# WATER_LEVEL_INDICATOR.net
KiCad netlist of a schematic drawn in EAGLE
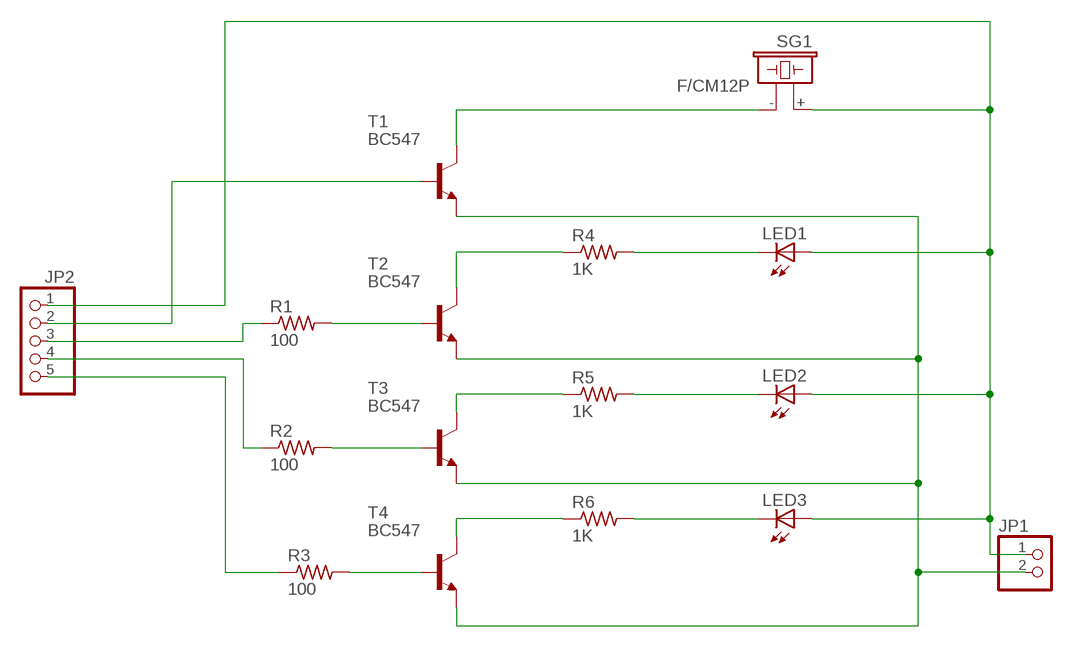
[diagram p0: schematic, sheet 1]

(export (version "E")
  (design (tool "Eeschema 10.0.6"))
  (components
    (comp (ref "JP1")
      (value "PINHD-1X2")
      (footprint "eagle-import:1X02")
      (libsource (lib "eagle-import") (part "PINHD-1X2"))
    )
    (comp (ref "JP2")
      (value "PINHD-1X5")
      (footprint "eagle-import:1X05")
      (libsource (lib "eagle-import") (part "PINHD-1X5"))
    )
    (comp (ref "LED1")
      (value "LED5MM")
      (footprint "eagle-import:LED5MM")
      (libsource (lib "eagle-import") (part "LED5MM"))
    )
    (comp (ref "LED2")
      (value "LED5MM")
      (footprint "eagle-import:LED5MM")
      (libsource (lib "eagle-import") (part "LED5MM"))
    )
    (comp (ref "LED3")
      (value "LED5MM")
      (footprint "eagle-import:LED5MM")
      (libsource (lib "eagle-import") (part "LED5MM"))
    )
    (comp (ref "R1")
      (value "100")
      (footprint "eagle-import:0207_10")
      (libsource (lib "eagle-import") (part "R-US_0207/10"))
    )
    (comp (ref "R2")
      (value "100")
      (footprint "eagle-import:0207_10")
      (libsource (lib "eagle-import") (part "R-US_0207/10"))
    )
    (comp (ref "R3")
      (value "100")
      (footprint "eagle-import:0207_10")
      (libsource (lib "eagle-import") (part "R-US_0207/10"))
    )
    (comp (ref "R4")
      (value "1K")
      (footprint "eagle-import:0207_10")
      (libsource (lib "eagle-import") (part "R-US_0207/10"))
    )
    (comp (ref "R5")
      (value "1K")
      (footprint "eagle-import:0207_10")
      (libsource (lib "eagle-import") (part "R-US_0207/10"))
    )
    (comp (ref "R6")
      (value "1K")
      (footprint "eagle-import:0207_10")
      (libsource (lib "eagle-import") (part "R-US_0207/10"))
    )
    (comp (ref "SG1")
      (value "F/CM12P")
      (footprint "eagle-import:F_CM12P")
      (libsource (lib "eagle-import") (part "F/CM12P"))
    )
    (comp (ref "T1")
      (value "BC547")
      (footprint "eagle-import:TO92")
      (libsource (lib "eagle-import") (part "BC547"))
    )
    (comp (ref "T2")
      (value "BC547")
      (footprint "eagle-import:TO92")
      (libsource (lib "eagle-import") (part "BC547"))
    )
    (comp (ref "T3")
      (value "BC547")
      (footprint "eagle-import:TO92")
      (libsource (lib "eagle-import") (part "BC547"))
    )
    (comp (ref "T4")
      (value "BC547")
      (footprint "eagle-import:TO92")
      (libsource (lib "eagle-import") (part "BC547"))
    )
  )
  (nets
    (net (code "1") (name "Net-(JP2-Pad3)") (class "Default")
      (node (ref "JP2") (pin "3") (pinfunction "3_3") (pintype "passive"))
      (node (ref "R1") (pin "1") (pinfunction "1_1") (pintype "passive"))
    )
    (net (code "2") (name "Net-(JP2-Pad4)") (class "Default")
      (node (ref "JP2") (pin "4") (pinfunction "4_4") (pintype "passive"))
      (node (ref "R2") (pin "1") (pinfunction "1_1") (pintype "passive"))
    )
    (net (code "3") (name "Net-(JP2-Pad5)") (class "Default")
      (node (ref "JP2") (pin "5") (pinfunction "5_5") (pintype "passive"))
      (node (ref "R3") (pin "1") (pinfunction "1_1") (pintype "passive"))
    )
    (net (code "4") (name "Net-(LED1-C)") (class "Default")
      (node (ref "LED1") (pin "K") (pinfunction "C_K") (pintype "passive"))
      (node (ref "R4") (pin "2") (pinfunction "2_2") (pintype "passive"))
    )
    (net (code "5") (name "Net-(LED2-C)") (class "Default")
      (node (ref "LED2") (pin "K") (pinfunction "C_K") (pintype "passive"))
      (node (ref "R5") (pin "2") (pinfunction "2_2") (pintype "passive"))
    )
    (net (code "6") (name "Net-(LED3-C)") (class "Default")
      (node (ref "LED3") (pin "K") (pinfunction "C_K") (pintype "passive"))
      (node (ref "R6") (pin "2") (pinfunction "2_2") (pintype "passive"))
    )
    (net (code "7") (name "Net-(SG1-1)") (class "Default")
      (node (ref "JP1") (pin "1") (pinfunction "1_1") (pintype "passive"))
      (node (ref "JP2") (pin "1") (pinfunction "1_1") (pintype "passive"))
      (node (ref "LED1") (pin "A") (pinfunction "A_A") (pintype "passive"))
      (node (ref "LED2") (pin "A") (pinfunction "A_A") (pintype "passive"))
      (node (ref "LED3") (pin "A") (pinfunction "A_A") (pintype "passive"))
      (node (ref "SG1") (pin "+") (pinfunction "1_+") (pintype "passive"))
    )
    (net (code "8") (name "Net-(SG1-2)") (class "Default")
      (node (ref "SG1") (pin "-") (pinfunction "2_-") (pintype "passive"))
      (node (ref "T1") (pin "3") (pinfunction "C_3") (pintype "passive"))
    )
    (net (code "9") (name "Net-(T1-B)") (class "Default")
      (node (ref "JP2") (pin "2") (pinfunction "2_2") (pintype "passive"))
      (node (ref "T1") (pin "2") (pinfunction "B_2") (pintype "passive"))
    )
    (net (code "10") (name "Net-(T1-E)") (class "Default")
      (node (ref "JP1") (pin "2") (pinfunction "2_2") (pintype "passive"))
      (node (ref "T1") (pin "1") (pinfunction "E_1") (pintype "passive"))
      (node (ref "T2") (pin "1") (pinfunction "E_1") (pintype "passive"))
      (node (ref "T3") (pin "1") (pinfunction "E_1") (pintype "passive"))
      (node (ref "T4") (pin "1") (pinfunction "E_1") (pintype "passive"))
    )
    (net (code "11") (name "Net-(T2-B)") (class "Default")
      (node (ref "R1") (pin "2") (pinfunction "2_2") (pintype "passive"))
      (node (ref "T2") (pin "2") (pinfunction "B_2") (pintype "passive"))
    )
    (net (code "12") (name "Net-(T2-C)") (class "Default")
      (node (ref "R4") (pin "1") (pinfunction "1_1") (pintype "passive"))
      (node (ref "T2") (pin "3") (pinfunction "C_3") (pintype "passive"))
    )
    (net (code "13") (name "Net-(T3-B)") (class "Default")
      (node (ref "R2") (pin "2") (pinfunction "2_2") (pintype "passive"))
      (node (ref "T3") (pin "2") (pinfunction "B_2") (pintype "passive"))
    )
    (net (code "14") (name "Net-(T3-C)") (class "Default")
      (node (ref "R5") (pin "1") (pinfunction "1_1") (pintype "passive"))
      (node (ref "T3") (pin "3") (pinfunction "C_3") (pintype "passive"))
    )
    (net (code "15") (name "Net-(T4-B)") (class "Default")
      (node (ref "R3") (pin "2") (pinfunction "2_2") (pintype "passive"))
      (node (ref "T4") (pin "2") (pinfunction "B_2") (pintype "passive"))
    )
    (net (code "16") (name "Net-(T4-C)") (class "Default")
      (node (ref "R6") (pin "1") (pinfunction "1_1") (pintype "passive"))
      (node (ref "T4") (pin "3") (pinfunction "C_3") (pintype "passive"))
    )
  )
)
